# INT_REG.net
KiCad netlist of a schematic drawn in Altium Designer
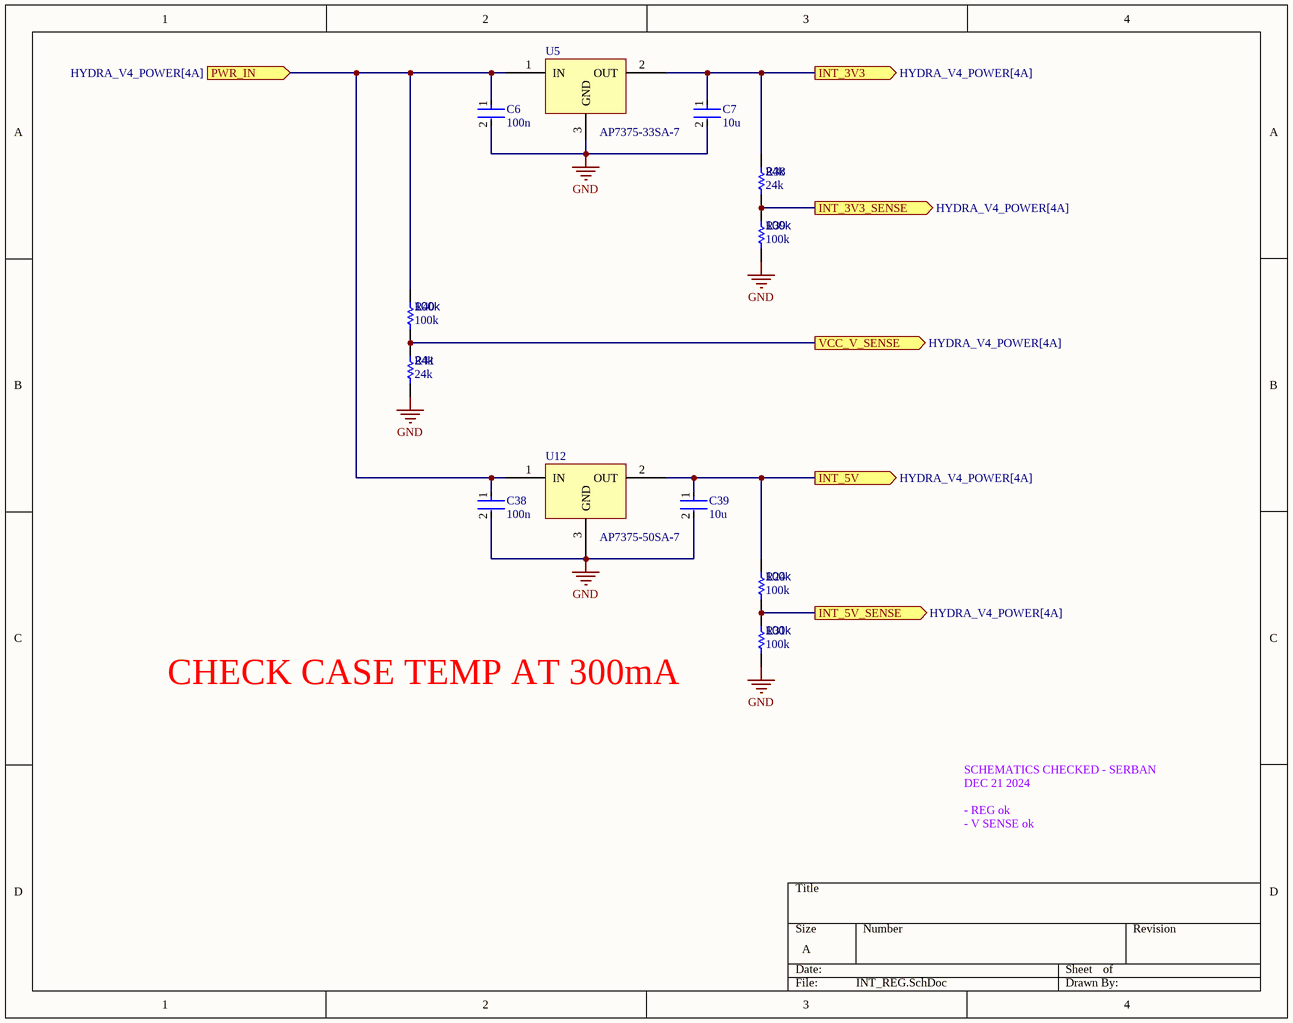
[diagram p0: INT_REG.SchDoc]

(export (version "E")
  (design (tool "Eeschema 10.0.6"))
  (components
    (comp (ref "C6")
      (value "100n")
      (footprint "FP-0402-L_1_0_0_05-W_0_5-IPC_A")
      (description "LARGE PADS, 0402 CAP, CHANGE COMMENT TO MATCH REAL P/N")
      (libsource (lib "Space Concordia") (part "b4654b650e69147ec39a6b967a45e02"))
    )
    (comp (ref "C7")
      (value "10u")
      (footprint "FP-0402-L_1_0_0_05-W_0_5-IPC_A")
      (description "LARGE PADS, 0402 CAP, CHANGE COMMENT TO MATCH REAL P/N")
      (libsource (lib "Space Concordia") (part "b4654b650e69147ec39a6b967a45e02"))
    )
    (comp (ref "C38")
      (value "100n")
      (footprint "FP-0402-L_1_0_0_05-W_0_5-IPC_A")
      (description "LARGE PADS, 0402 CAP, CHANGE COMMENT TO MATCH REAL P/N")
      (libsource (lib "Space Concordia") (part "b4654b650e69147ec39a6b967a45e02"))
    )
    (comp (ref "C39")
      (value "10u")
      (footprint "FP-0402-L_1_0_0_05-W_0_5-IPC_A")
      (description "LARGE PADS, 0402 CAP, CHANGE COMMENT TO MATCH REAL P/N")
      (libsource (lib "Space Concordia") (part "b4654b650e69147ec39a6b967a45e02"))
    )
    (comp (ref "R24")
      (value "100k")
      (footprint "R0603B")
      (description "Resistor")
      (fields (field (name "ALTIUM_VALUE") "100k"))
      (libsource (lib "Space Concordia") (part "Resistor"))
    )
    (comp (ref "R31")
      (value "100k")
      (footprint "R0603B")
      (description "Resistor")
      (fields (field (name "ALTIUM_VALUE") "100k"))
      (libsource (lib "Space Concordia") (part "Resistor"))
    )
    (comp (ref "R38")
      (value "24k")
      (footprint "R0603B")
      (description "Resistor")
      (fields (field (name "ALTIUM_VALUE") "24k"))
      (libsource (lib "Space Concordia") (part "Resistor"))
    )
    (comp (ref "R39")
      (value "100k")
      (footprint "R0603B")
      (description "Resistor")
      (fields (field (name "ALTIUM_VALUE") "100k"))
      (libsource (lib "Space Concordia") (part "Resistor"))
    )
    (comp (ref "R40")
      (value "100k")
      (footprint "R0603B")
      (description "Resistor")
      (fields (field (name "ALTIUM_VALUE") "100k"))
      (libsource (lib "Space Concordia") (part "Resistor"))
    )
    (comp (ref "R41")
      (value "24k")
      (footprint "R0603B")
      (description "Resistor")
      (fields (field (name "ALTIUM_VALUE") "24k"))
      (libsource (lib "Space Concordia") (part "Resistor"))
    )
    (comp (ref "U5")
      (value "AP7375-33SA-7")
      (footprint "SOT90P285X110-3N")
      (description "LDO Regulator Pos 3.3V 0.3A 3-Pin SOT-23 T/R")
      (libsource (lib "Space Concordia") (part "AP7375-33SA-7"))
    )
    (comp (ref "U12")
      (value "AP7375-50SA-7")
      (footprint "AP7375-50SA-7-Footprint-1")
      (description "Ldo Cmos Lowcurr SOT23 T&r 3K")
      (libsource (lib "Space Concordia") (part "AP7375-50SA-7"))
    )
  )
  (nets
    (net (code "1") (name "/INT_3V3") (class "Default")
      (node (ref "C7") (pin "1") (pinfunction "1_1") (pintype "passive"))
      (node (ref "R38") (pin "2") (pinfunction "2_2") (pintype "passive"))
      (node (ref "U5") (pin "2") (pinfunction "OUT_2") (pintype "passive"))
    )
    (net (code "2") (name "/INT_3V3_SENSE") (class "Default")
      (node (ref "R38") (pin "1") (pinfunction "1_1") (pintype "passive"))
      (node (ref "R39") (pin "2") (pinfunction "2_2") (pintype "passive"))
    )
    (net (code "3") (name "/INT_5V") (class "Default")
      (node (ref "C39") (pin "1") (pinfunction "1_1") (pintype "passive"))
      (node (ref "R24") (pin "2") (pinfunction "2_2") (pintype "passive"))
      (node (ref "U12") (pin "2") (pinfunction "OUT_2") (pintype "passive"))
    )
    (net (code "4") (name "/INT_5V_SENSE") (class "Default")
      (node (ref "R24") (pin "1") (pinfunction "1_1") (pintype "passive"))
      (node (ref "R31") (pin "2") (pinfunction "2_2") (pintype "passive"))
    )
    (net (code "5") (name "/PWR_IN") (class "Default")
      (node (ref "C38") (pin "1") (pinfunction "1_1") (pintype "passive"))
      (node (ref "C6") (pin "1") (pinfunction "1_1") (pintype "passive"))
      (node (ref "R40") (pin "2") (pinfunction "2_2") (pintype "passive"))
      (node (ref "U12") (pin "1") (pinfunction "IN_1") (pintype "passive"))
      (node (ref "U5") (pin "1") (pinfunction "IN_1") (pintype "passive"))
    )
    (net (code "6") (name "/VCC_V_SENSE") (class "Default")
      (node (ref "R40") (pin "1") (pinfunction "1_1") (pintype "passive"))
      (node (ref "R41") (pin "2") (pinfunction "2_2") (pintype "passive"))
    )
    (net (code "7") (name "GND") (class "Default")
      (node (ref "C38") (pin "2") (pinfunction "2_2") (pintype "passive"))
      (node (ref "C39") (pin "2") (pinfunction "2_2") (pintype "passive"))
      (node (ref "C6") (pin "2") (pinfunction "2_2") (pintype "passive"))
      (node (ref "C7") (pin "2") (pinfunction "2_2") (pintype "passive"))
      (node (ref "R31") (pin "1") (pinfunction "1_1") (pintype "passive"))
      (node (ref "R39") (pin "1") (pinfunction "1_1") (pintype "passive"))
      (node (ref "R41") (pin "1") (pinfunction "1_1") (pintype "passive"))
      (node (ref "U12") (pin "3") (pinfunction "GND_3") (pintype "passive"))
      (node (ref "U5") (pin "3") (pinfunction "GND_3") (pintype "passive"))
    )
  )
)
